# act_pot_diff.net
KiCad netlist of a schematic drawn in EAGLE
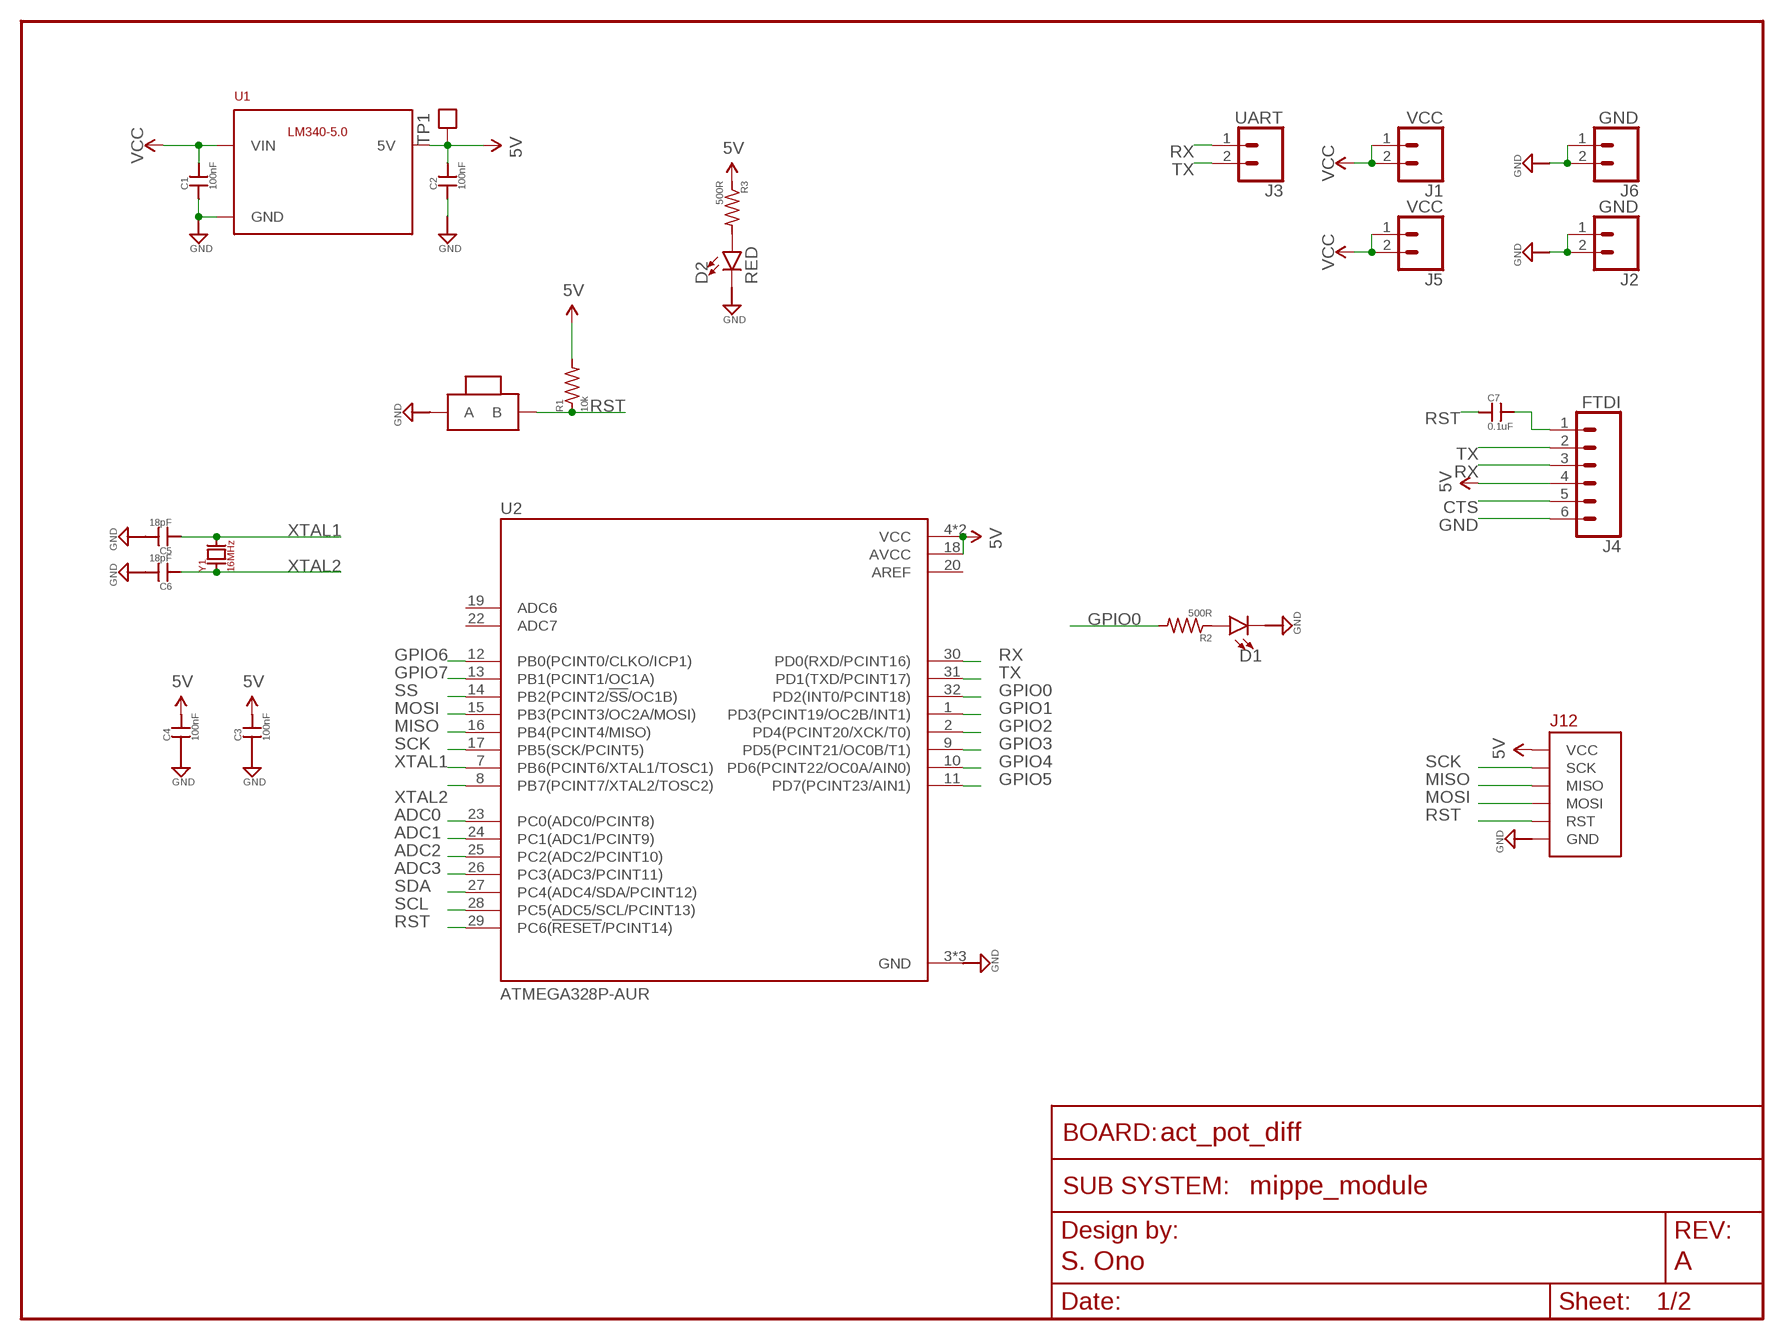
[diagram p0: schematic, sheet 1]
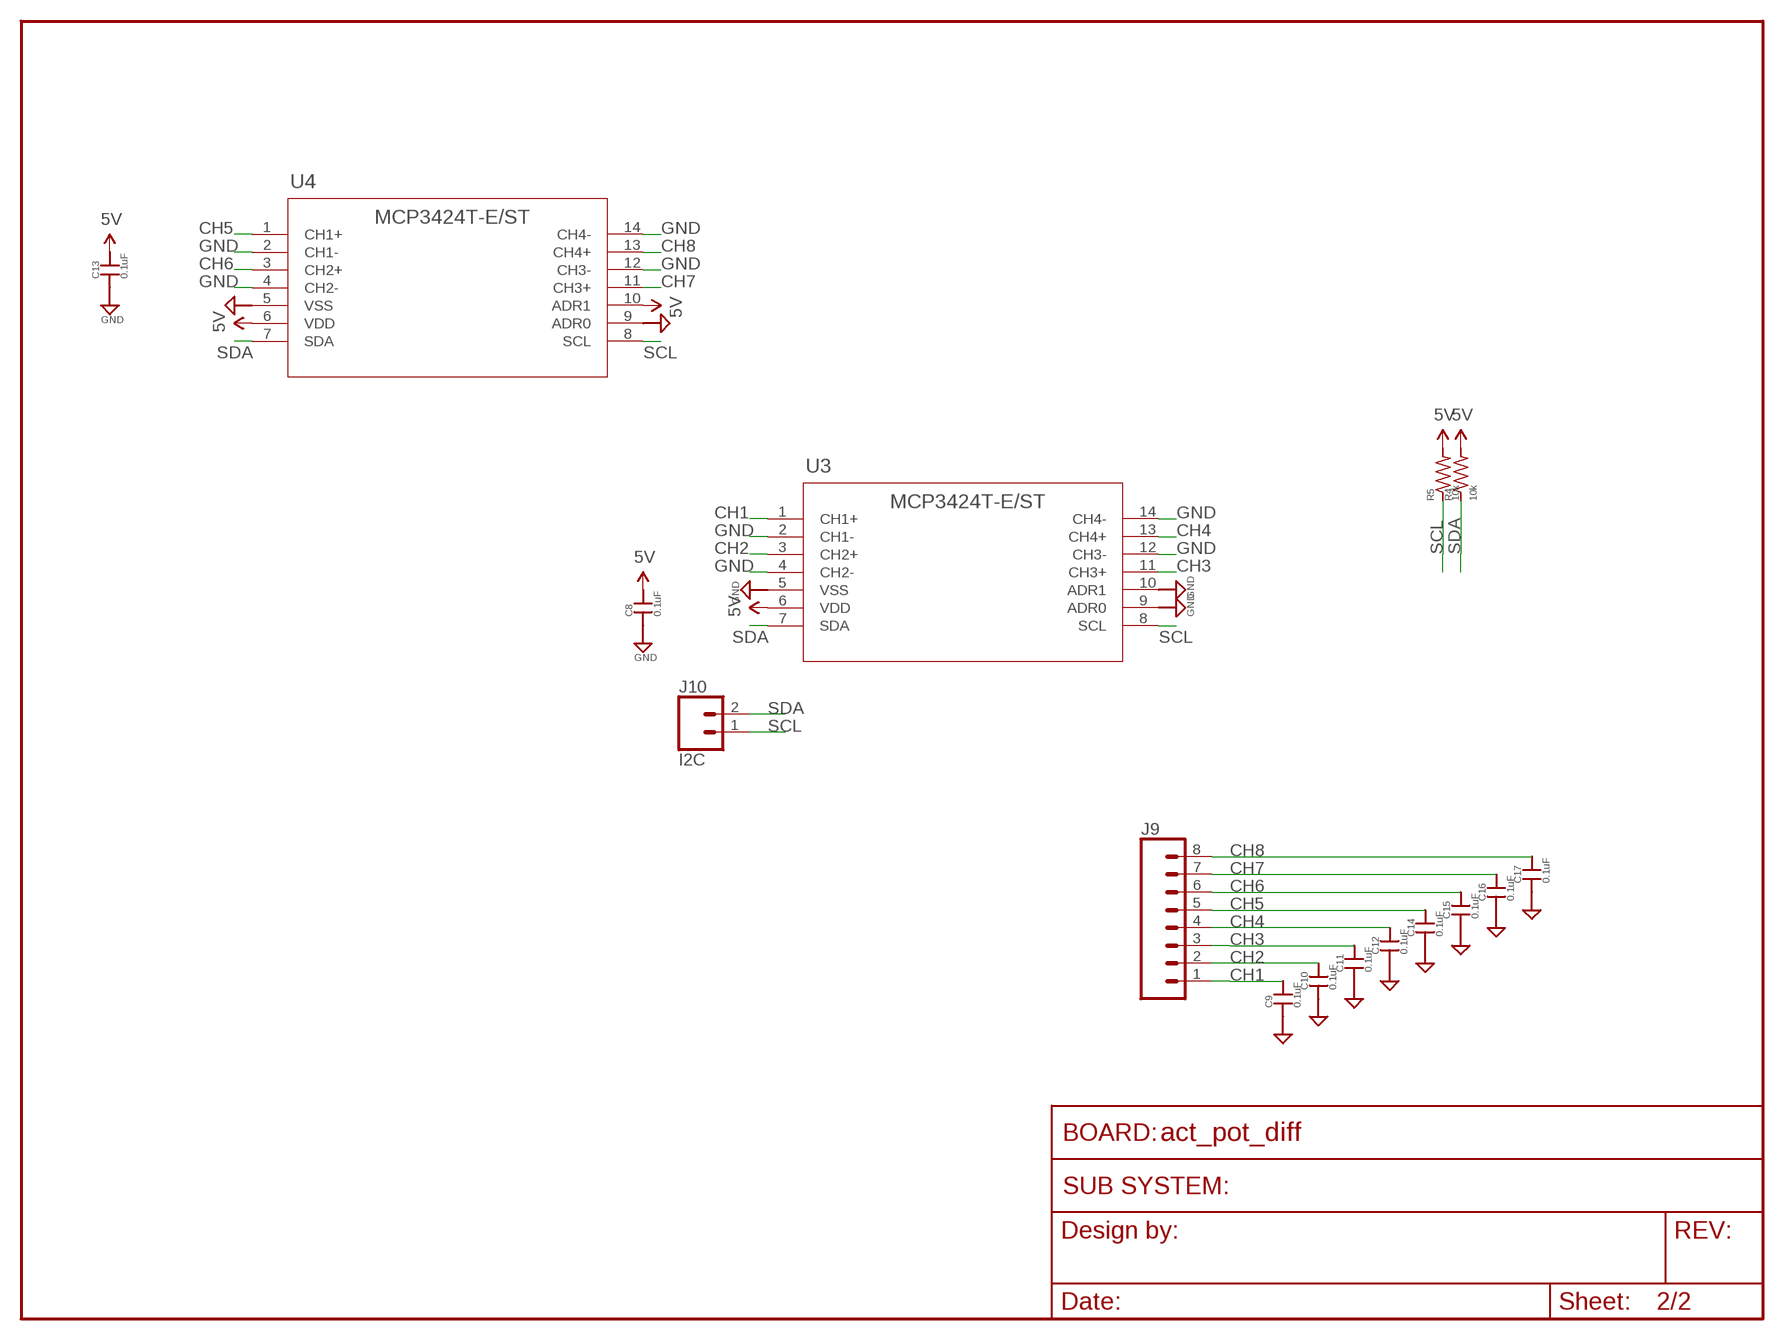
[diagram p1: schematic, sheet 2]

(export (version "E")
  (design (tool "Eeschema 10.0.6"))
  (components
    (comp (ref "C1")
      (value "100nF")
      (footprint "eagle-import:0402-CAP")
      (libsource (lib "eagle-import") (part "CAP0402-CAP"))
    )
    (comp (ref "C2")
      (value "100nF")
      (footprint "eagle-import:0402-CAP")
      (libsource (lib "eagle-import") (part "CAP0402-CAP"))
    )
    (comp (ref "C3")
      (value "100nF")
      (footprint "eagle-import:0402-CAP")
      (libsource (lib "eagle-import") (part "CAP0402-CAP"))
    )
    (comp (ref "C4")
      (value "100nF")
      (footprint "eagle-import:0402-CAP")
      (libsource (lib "eagle-import") (part "CAP0402-CAP"))
    )
    (comp (ref "C5")
      (value "18pF")
      (footprint "eagle-import:0402-CAP")
      (libsource (lib "eagle-import") (part "CAP0402-CAP"))
    )
    (comp (ref "C6")
      (value "18pF")
      (footprint "eagle-import:0402-CAP")
      (libsource (lib "eagle-import") (part "CAP0402-CAP"))
    )
    (comp (ref "C7")
      (value "0.1uF")
      (footprint "eagle-import:0402-CAP")
      (libsource (lib "eagle-import") (part "CAP0402-CAP"))
    )
    (comp (ref "D1")
      (value "LED0603")
      (footprint "eagle-import:LED-0603")
      (libsource (lib "eagle-import") (part "LED0603"))
    )
    (comp (ref "D2")
      (value "RED")
      (footprint "eagle-import:LED-0603")
      (libsource (lib "eagle-import") (part "LED0603"))
    )
    (comp (ref "J1")
      (value "VCC")
      (footprint "eagle-import:1X02")
      (libsource (lib "eagle-import") (part "CONN_02"))
    )
    (comp (ref "J2")
      (value "GND")
      (footprint "eagle-import:1X02")
      (libsource (lib "eagle-import") (part "CONN_02"))
    )
    (comp (ref "J3")
      (value "UART")
      (footprint "eagle-import:1X02")
      (libsource (lib "eagle-import") (part "CONN_02"))
    )
    (comp (ref "J4")
      (value "FTDI")
      (footprint "eagle-import:1X06_NO_SILK")
      (libsource (lib "eagle-import") (part "CONN_06NO_SILK_FEMALE_PTH"))
    )
    (comp (ref "J5")
      (value "VCC")
      (footprint "eagle-import:1X02")
      (libsource (lib "eagle-import") (part "CONN_02"))
    )
    (comp (ref "J6")
      (value "GND")
      (footprint "eagle-import:1X02")
      (libsource (lib "eagle-import") (part "CONN_02"))
    )
    (comp (ref "J12")
      (value "BURNIN")
      (footprint "eagle-import:BURNIN")
      (libsource (lib "eagle-import") (part "BURNIN"))
    )
    (comp (ref "R1")
      (value "10k")
      (footprint "eagle-import:R0402")
      (libsource (lib "eagle-import") (part "R-US_R0402"))
    )
    (comp (ref "R2")
      (value "500R")
      (footprint "eagle-import:R0402")
      (libsource (lib "eagle-import") (part "R-US_R0402"))
    )
    (comp (ref "R3")
      (value "500R")
      (footprint "eagle-import:R0402")
      (libsource (lib "eagle-import") (part "R-US_R0402"))
    )
    (comp (ref "SW1")
      (value "BTN-PTS810")
      (footprint "eagle-import:BTN_PTS810")
      (libsource (lib "eagle-import") (part "BTN-PTS810"))
    )
    (comp (ref "TP1")
      (value "TEST_POINTTHRU")
      (footprint "eagle-import:TEST_POINT")
      (libsource (lib "eagle-import") (part "TEST_POINTTHRU"))
    )
    (comp (ref "U1")
      (value "LM340MPX-5.0230")
      (footprint "eagle-import:SOT230P700X180-4N")
      (libsource (lib "eagle-import") (part "LM340MPX-5.0230"))
    )
    (comp (ref "U2")
      (value "ATMEGA328P-AUR")
      (footprint "eagle-import:QFP80P900X900X120-32N")
      (fields (field (name "DIGI-KEY_PART_NUMBER") "ATMEGA328P-AURCT-ND") (field (name "MF") "Microchip"))
      (libsource (lib "eagle-import") (part "ATMEGA328P-AUR"))
    )
    (comp (ref "Y1")
      (value "16MHz")
      (footprint "eagle-import:XTAL500X320X130N")
      (libsource (lib "eagle-import") (part "CRYSTAL_SMOL"))
    )
    (comp (ref "C8")
      (value "0.1uF")
      (footprint "eagle-import:0603-CAP")
      (libsource (lib "eagle-import") (part "CAP0603-CAP"))
    )
    (comp (ref "C9")
      (value "0.1uF")
      (footprint "eagle-import:0402-CAP")
      (libsource (lib "eagle-import") (part "CAP0402-CAP"))
    )
    (comp (ref "C10")
      (value "0.1uF")
      (footprint "eagle-import:0402-CAP")
      (libsource (lib "eagle-import") (part "CAP0402-CAP"))
    )
    (comp (ref "C11")
      (value "0.1uF")
      (footprint "eagle-import:0402-CAP")
      (libsource (lib "eagle-import") (part "CAP0402-CAP"))
    )
    (comp (ref "C12")
      (value "0.1uF")
      (footprint "eagle-import:0402-CAP")
      (libsource (lib "eagle-import") (part "CAP0402-CAP"))
    )
    (comp (ref "C13")
      (value "0.1uF")
      (footprint "eagle-import:0603-CAP")
      (libsource (lib "eagle-import") (part "CAP0603-CAP"))
    )
    (comp (ref "C14")
      (value "0.1uF")
      (footprint "eagle-import:0402-CAP")
      (libsource (lib "eagle-import") (part "CAP0402-CAP"))
    )
    (comp (ref "C15")
      (value "0.1uF")
      (footprint "eagle-import:0402-CAP")
      (libsource (lib "eagle-import") (part "CAP0402-CAP"))
    )
    (comp (ref "C16")
      (value "0.1uF")
      (footprint "eagle-import:0402-CAP")
      (libsource (lib "eagle-import") (part "CAP0402-CAP"))
    )
    (comp (ref "C17")
      (value "0.1uF")
      (footprint "eagle-import:0402-CAP")
      (libsource (lib "eagle-import") (part "CAP0402-CAP"))
    )
    (comp (ref "J9")
      (value "CONN_08\"")
      (footprint "eagle-import:1X08")
      (libsource (lib "eagle-import") (part "CONN_08{dblquote}"))
    )
    (comp (ref "J10")
      (value "I2C")
      (footprint "eagle-import:1X02")
      (libsource (lib "eagle-import") (part "CONN_02"))
    )
    (comp (ref "R4")
      (value "10k")
      (footprint "eagle-import:R0402")
      (libsource (lib "eagle-import") (part "R-US_R0402"))
    )
    (comp (ref "R5")
      (value "10k")
      (footprint "eagle-import:R0402")
      (libsource (lib "eagle-import") (part "R-US_R0402"))
    )
    (comp (ref "U3")
      (value "MCP3424T-E/ST")
      (footprint "eagle-import:TSSOP14_MC")
      (fields (field (name "MANUFACTURER_PART_NUMBER") "MCP3424TEST"))
      (libsource (lib "eagle-import") (part "MCP3424T-E/ST"))
    )
    (comp (ref "U4")
      (value "MCP3424T-E/ST")
      (footprint "eagle-import:TSSOP14_MC")
      (fields (field (name "MANUFACTURER_PART_NUMBER") "MCP3424TEST"))
      (libsource (lib "eagle-import") (part "MCP3424T-E/ST"))
    )
  )
  (nets
    (net (code "1") (name "5V") (class "Default")
      (node (ref "C13") (pin "2") (pinfunction "2_2") (pintype "passive"))
      (node (ref "C2") (pin "2") (pinfunction "2_2") (pintype "passive"))
      (node (ref "C3") (pin "2") (pinfunction "2_2") (pintype "passive"))
      (node (ref "C4") (pin "2") (pinfunction "2_2") (pintype "passive"))
      (node (ref "C8") (pin "2") (pinfunction "2_2") (pintype "passive"))
      (node (ref "J12") (pin "3.3V") (pinfunction "VCC_3.3V") (pintype "power_in"))
      (node (ref "J4") (pin "4") (pinfunction "4_4") (pintype "passive"))
      (node (ref "R1") (pin "2") (pinfunction "2_2") (pintype "passive"))
      (node (ref "R3") (pin "1") (pinfunction "1_1") (pintype "passive"))
      (node (ref "R4") (pin "2") (pinfunction "2_2") (pintype "passive"))
      (node (ref "R5") (pin "2") (pinfunction "2_2") (pintype "passive"))
      (node (ref "TP1") (pin "1") (pinfunction "P$1_1") (pintype "bidirectional"))
      (node (ref "U1") (pin "3") (pinfunction "5V_3") (pintype "power_in"))
      (node (ref "U2") (pin "18") (pinfunction "AVCC_18") (pintype "power_in"))
      (node (ref "U2") (pin "4") (pinfunction "VCC_4") (pintype "power_in"))
      (node (ref "U2") (pin "6") (pinfunction "VCC_6") (pintype "power_in"))
      (node (ref "U3") (pin "6") (pinfunction "VDD_6") (pintype "power_in"))
      (node (ref "U4") (pin "10") (pinfunction "ADR1_10") (pintype "passive"))
      (node (ref "U4") (pin "6") (pinfunction "VDD_6") (pintype "power_in"))
    )
    (net (code "2") (name "ADC0") (class "Default")
      (node (ref "U2") (pin "23") (pinfunction "PC0(ADC0/PCINT8)_23") (pintype "bidirectional"))
    )
    (net (code "3") (name "ADC1") (class "Default")
      (node (ref "U2") (pin "24") (pinfunction "PC1(ADC1/PCINT9)_24") (pintype "bidirectional"))
    )
    (net (code "4") (name "ADC2") (class "Default")
      (node (ref "U2") (pin "25") (pinfunction "PC2(ADC2/PCINT10)_25") (pintype "bidirectional"))
    )
    (net (code "5") (name "ADC3") (class "Default")
      (node (ref "U2") (pin "26") (pinfunction "PC3(ADC3/PCINT11)_26") (pintype "bidirectional"))
    )
    (net (code "6") (name "AREF") (class "Default")
      (node (ref "U2") (pin "20") (pinfunction "AREF_20") (pintype "power_in"))
    )
    (net (code "7") (name "CH1") (class "Default")
      (node (ref "C9") (pin "2") (pinfunction "2_2") (pintype "passive"))
      (node (ref "J9") (pin "1") (pinfunction "1_1") (pintype "passive"))
      (node (ref "U3") (pin "1") (pinfunction "CH1+_1") (pintype "input"))
    )
    (net (code "8") (name "CH2") (class "Default")
      (node (ref "C10") (pin "2") (pinfunction "2_2") (pintype "passive"))
      (node (ref "J9") (pin "2") (pinfunction "2_2") (pintype "passive"))
      (node (ref "U3") (pin "3") (pinfunction "CH2+_3") (pintype "input"))
    )
    (net (code "9") (name "CH3") (class "Default")
      (node (ref "C11") (pin "2") (pinfunction "2_2") (pintype "passive"))
      (node (ref "J9") (pin "3") (pinfunction "3_3") (pintype "passive"))
      (node (ref "U3") (pin "11") (pinfunction "CH3+_11") (pintype "input"))
    )
    (net (code "10") (name "CH4") (class "Default")
      (node (ref "C12") (pin "2") (pinfunction "2_2") (pintype "passive"))
      (node (ref "J9") (pin "4") (pinfunction "4_4") (pintype "passive"))
      (node (ref "U3") (pin "13") (pinfunction "CH4+_13") (pintype "input"))
    )
    (net (code "11") (name "CH5") (class "Default")
      (node (ref "C14") (pin "2") (pinfunction "2_2") (pintype "passive"))
      (node (ref "J9") (pin "5") (pinfunction "5_5") (pintype "passive"))
      (node (ref "U4") (pin "1") (pinfunction "CH1+_1") (pintype "input"))
    )
    (net (code "12") (name "CH6") (class "Default")
      (node (ref "C15") (pin "2") (pinfunction "2_2") (pintype "passive"))
      (node (ref "J9") (pin "6") (pinfunction "6_6") (pintype "passive"))
      (node (ref "U4") (pin "3") (pinfunction "CH2+_3") (pintype "input"))
    )
    (net (code "13") (name "CH7") (class "Default")
      (node (ref "C16") (pin "2") (pinfunction "2_2") (pintype "passive"))
      (node (ref "J9") (pin "7") (pinfunction "7_7") (pintype "passive"))
      (node (ref "U4") (pin "11") (pinfunction "CH3+_11") (pintype "input"))
    )
    (net (code "14") (name "CH8") (class "Default")
      (node (ref "C17") (pin "2") (pinfunction "2_2") (pintype "passive"))
      (node (ref "J9") (pin "8") (pinfunction "8_8") (pintype "passive"))
      (node (ref "U4") (pin "13") (pinfunction "CH4+_13") (pintype "input"))
    )
    (net (code "15") (name "CTS") (class "Default")
      (node (ref "J4") (pin "5") (pinfunction "5_5") (pintype "passive"))
    )
    (net (code "16") (name "GND") (class "Default")
      (node (ref "C1") (pin "1") (pinfunction "1_1") (pintype "passive"))
      (node (ref "C10") (pin "1") (pinfunction "1_1") (pintype "passive"))
      (node (ref "C11") (pin "1") (pinfunction "1_1") (pintype "passive"))
      (node (ref "C12") (pin "1") (pinfunction "1_1") (pintype "passive"))
      (node (ref "C13") (pin "1") (pinfunction "1_1") (pintype "passive"))
      (node (ref "C14") (pin "1") (pinfunction "1_1") (pintype "passive"))
      (node (ref "C15") (pin "1") (pinfunction "1_1") (pintype "passive"))
      (node (ref "C16") (pin "1") (pinfunction "1_1") (pintype "passive"))
      (node (ref "C17") (pin "1") (pinfunction "1_1") (pintype "passive"))
      (node (ref "C2") (pin "1") (pinfunction "1_1") (pintype "passive"))
      (node (ref "C3") (pin "1") (pinfunction "1_1") (pintype "passive"))
      (node (ref "C4") (pin "1") (pinfunction "1_1") (pintype "passive"))
      (node (ref "C5") (pin "2") (pinfunction "2_2") (pintype "passive"))
      (node (ref "C6") (pin "2") (pinfunction "2_2") (pintype "passive"))
      (node (ref "C8") (pin "1") (pinfunction "1_1") (pintype "passive"))
      (node (ref "C9") (pin "1") (pinfunction "1_1") (pintype "passive"))
      (node (ref "D1") (pin "C") (pinfunction "C_C") (pintype "passive"))
      (node (ref "D2") (pin "C") (pinfunction "C_C") (pintype "passive"))
      (node (ref "J12") (pin "GND") (pinfunction "GND_GND") (pintype "power_in"))
      (node (ref "J2") (pin "1") (pinfunction "1_1") (pintype "passive"))
      (node (ref "J2") (pin "2") (pinfunction "2_2") (pintype "passive"))
      (node (ref "J4") (pin "6") (pinfunction "6_6") (pintype "passive"))
      (node (ref "J6") (pin "1") (pinfunction "1_1") (pintype "passive"))
      (node (ref "J6") (pin "2") (pinfunction "2_2") (pintype "passive"))
      (node (ref "SW1") (pin "1") (pinfunction "A_1") (pintype "bidirectional"))
      (node (ref "SW1") (pin "2") (pinfunction "A_2") (pintype "bidirectional"))
      (node (ref "U1") (pin "2") (pinfunction "GND_2") (pintype "power_in"))
      (node (ref "U1") (pin "4") (pinfunction "GND_4") (pintype "power_in"))
      (node (ref "U2") (pin "21") (pinfunction "GND_21") (pintype "power_in"))
      (node (ref "U2") (pin "3") (pinfunction "GND_3") (pintype "power_in"))
      (node (ref "U2") (pin "5") (pinfunction "GND_5") (pintype "power_in"))
      (node (ref "U3") (pin "10") (pinfunction "ADR1_10") (pintype "passive"))
      (node (ref "U3") (pin "12") (pinfunction "CH3-_12") (pintype "input"))
      (node (ref "U3") (pin "14") (pinfunction "CH4-_14") (pintype "input"))
      (node (ref "U3") (pin "2") (pinfunction "CH1-_2") (pintype "input"))
      (node (ref "U3") (pin "4") (pinfunction "CH2-_4") (pintype "input"))
      (node (ref "U3") (pin "5") (pinfunction "VSS_5") (pintype "power_in"))
      (node (ref "U3") (pin "9") (pinfunction "ADR0_9") (pintype "passive"))
      (node (ref "U4") (pin "12") (pinfunction "CH3-_12") (pintype "input"))
      (node (ref "U4") (pin "14") (pinfunction "CH4-_14") (pintype "input"))
      (node (ref "U4") (pin "2") (pinfunction "CH1-_2") (pintype "input"))
      (node (ref "U4") (pin "4") (pinfunction "CH2-_4") (pintype "input"))
      (node (ref "U4") (pin "5") (pinfunction "VSS_5") (pintype "power_in"))
      (node (ref "U4") (pin "9") (pinfunction "ADR0_9") (pintype "passive"))
    )
    (net (code "17") (name "GPIO0") (class "Default")
      (node (ref "R2") (pin "2") (pinfunction "2_2") (pintype "passive"))
      (node (ref "U2") (pin "32") (pinfunction "PD2(INT0/PCINT18)_32") (pintype "bidirectional"))
    )
    (net (code "18") (name "GPIO1") (class "Default")
      (node (ref "U2") (pin "1") (pinfunction "PD3(PCINT19/OC2B/INT1)_1") (pintype "bidirectional"))
    )
    (net (code "19") (name "GPIO2") (class "Default")
      (node (ref "U2") (pin "2") (pinfunction "PD4(PCINT20/XCK/T0)_2") (pintype "bidirectional"))
    )
    (net (code "20") (name "GPIO3") (class "Default")
      (node (ref "U2") (pin "9") (pinfunction "PD5(PCINT21/OC0B/T1)_9") (pintype "bidirectional"))
    )
    (net (code "21") (name "GPIO4") (class "Default")
      (node (ref "U2") (pin "10") (pinfunction "PD6(PCINT22/OC0A/AIN0)_10") (pintype "bidirectional"))
    )
    (net (code "22") (name "GPIO5") (class "Default")
      (node (ref "U2") (pin "11") (pinfunction "PD7(PCINT23/AIN1)_11") (pintype "bidirectional"))
    )
    (net (code "23") (name "GPIO6") (class "Default")
      (node (ref "U2") (pin "12") (pinfunction "PB0(PCINT0/CLKO/ICP1)_12") (pintype "bidirectional"))
    )
    (net (code "24") (name "GPIO7") (class "Default")
      (node (ref "U2") (pin "13") (pinfunction "PB1(PCINT1/OC1A)_13") (pintype "bidirectional"))
    )
    (net (code "25") (name "MISO") (class "Default")
      (node (ref "J12") (pin "MISO") (pinfunction "MISO_MISO") (pintype "bidirectional"))
      (node (ref "U2") (pin "16") (pinfunction "PB4(PCINT4/MISO)_16") (pintype "bidirectional"))
    )
    (net (code "26") (name "MOSI") (class "Default")
      (node (ref "J12") (pin "MOSI") (pinfunction "MOSI_MOSI") (pintype "bidirectional"))
      (node (ref "U2") (pin "15") (pinfunction "PB3(PCINT3/OC2A/MOSI)_15") (pintype "bidirectional"))
    )
    (net (code "27") (name "Net-(C7-Pad2)") (class "Default")
      (node (ref "C7") (pin "2") (pinfunction "2_2") (pintype "passive"))
      (node (ref "J4") (pin "1") (pinfunction "1_1") (pintype "passive"))
    )
    (net (code "28") (name "Net-(D1-PadA)") (class "Default")
      (node (ref "D1") (pin "A") (pinfunction "A_A") (pintype "passive"))
      (node (ref "R2") (pin "1") (pinfunction "1_1") (pintype "passive"))
    )
    (net (code "29") (name "Net-(D2-PadA)") (class "Default")
      (node (ref "D2") (pin "A") (pinfunction "A_A") (pintype "passive"))
      (node (ref "R3") (pin "2") (pinfunction "2_2") (pintype "passive"))
    )
    (net (code "30") (name "RST") (class "Default")
      (node (ref "C7") (pin "1") (pinfunction "1_1") (pintype "passive"))
      (node (ref "J12") (pin "RST") (pinfunction "RST_RST") (pintype "bidirectional"))
      (node (ref "R1") (pin "1") (pinfunction "1_1") (pintype "passive"))
      (node (ref "SW1") (pin "3") (pinfunction "B_3") (pintype "bidirectional"))
      (node (ref "SW1") (pin "4") (pinfunction "B_4") (pintype "bidirectional"))
      (node (ref "U2") (pin "29") (pinfunction "PC6(~{RESET}/PCINT14)_29") (pintype "bidirectional"))
    )
    (net (code "31") (name "RX") (class "Default")
      (node (ref "J3") (pin "1") (pinfunction "1_1") (pintype "passive"))
      (node (ref "J4") (pin "3") (pinfunction "3_3") (pintype "passive"))
      (node (ref "U2") (pin "30") (pinfunction "PD0(RXD/PCINT16)_30") (pintype "bidirectional"))
    )
    (net (code "32") (name "SCK") (class "Default")
      (node (ref "J12") (pin "SCK") (pinfunction "SCK_SCK") (pintype "bidirectional"))
      (node (ref "U2") (pin "17") (pinfunction "PB5(SCK/PCINT5)_17") (pintype "bidirectional"))
    )
    (net (code "33") (name "SCL") (class "Default")
      (node (ref "J10") (pin "1") (pinfunction "1_1") (pintype "passive"))
      (node (ref "R5") (pin "1") (pinfunction "1_1") (pintype "passive"))
      (node (ref "U2") (pin "28") (pinfunction "PC5(ADC5/SCL/PCINT13)_28") (pintype "bidirectional"))
      (node (ref "U3") (pin "8") (pinfunction "SCL_8") (pintype "input"))
      (node (ref "U4") (pin "8") (pinfunction "SCL_8") (pintype "input"))
    )
    (net (code "34") (name "SDA") (class "Default")
      (node (ref "J10") (pin "2") (pinfunction "2_2") (pintype "passive"))
      (node (ref "R4") (pin "1") (pinfunction "1_1") (pintype "passive"))
      (node (ref "U2") (pin "27") (pinfunction "PC4(ADC4/SDA/PCINT12)_27") (pintype "bidirectional"))
      (node (ref "U3") (pin "7") (pinfunction "SDA_7") (pintype "bidirectional"))
      (node (ref "U4") (pin "7") (pinfunction "SDA_7") (pintype "bidirectional"))
    )
    (net (code "35") (name "SS") (class "Default")
      (node (ref "U2") (pin "14") (pinfunction "PB2(PCINT2/~{SS}/OC1B)_14") (pintype "bidirectional"))
    )
    (net (code "36") (name "TX") (class "Default")
      (node (ref "J3") (pin "2") (pinfunction "2_2") (pintype "passive"))
      (node (ref "J4") (pin "2") (pinfunction "2_2") (pintype "passive"))
      (node (ref "U2") (pin "31") (pinfunction "PD1(TXD/PCINT17)_31") (pintype "bidirectional"))
    )
    (net (code "37") (name "VCC") (class "Default")
      (node (ref "C1") (pin "2") (pinfunction "2_2") (pintype "passive"))
      (node (ref "J1") (pin "1") (pinfunction "1_1") (pintype "passive"))
      (node (ref "J1") (pin "2") (pinfunction "2_2") (pintype "passive"))
      (node (ref "J5") (pin "1") (pinfunction "1_1") (pintype "passive"))
      (node (ref "J5") (pin "2") (pinfunction "2_2") (pintype "passive"))
      (node (ref "U1") (pin "1") (pinfunction "VIN_1") (pintype "power_in"))
    )
    (net (code "38") (name "XTAL1") (class "Default")
      (node (ref "C5") (pin "1") (pinfunction "1_1") (pintype "passive"))
      (node (ref "U2") (pin "7") (pinfunction "PB6(PCINT6/XTAL1/TOSC1)_7") (pintype "bidirectional"))
      (node (ref "Y1") (pin "2") (pinfunction "B_2") (pintype "passive"))
    )
    (net (code "39") (name "XTAL2") (class "Default")
      (node (ref "C6") (pin "1") (pinfunction "1_1") (pintype "passive"))
      (node (ref "U2") (pin "8") (pinfunction "PB7(PCINT7/XTAL2/TOSC2)_8") (pintype "bidirectional"))
      (node (ref "Y1") (pin "1") (pinfunction "A_1") (pintype "passive"))
    )
    (net (code "40") (name "unconnected-(U2-ADC6-Pad19)") (class "Default")
      (node (ref "U2") (pin "19") (pinfunction "ADC6_19") (pintype "input"))
    )
    (net (code "41") (name "unconnected-(U2-ADC7-Pad22)") (class "Default")
      (node (ref "U2") (pin "22") (pinfunction "ADC7_22") (pintype "input"))
    )
  )
)
